# soundboard-qtpy-bff-v01.net
KiCad netlist of a schematic drawn in EAGLE
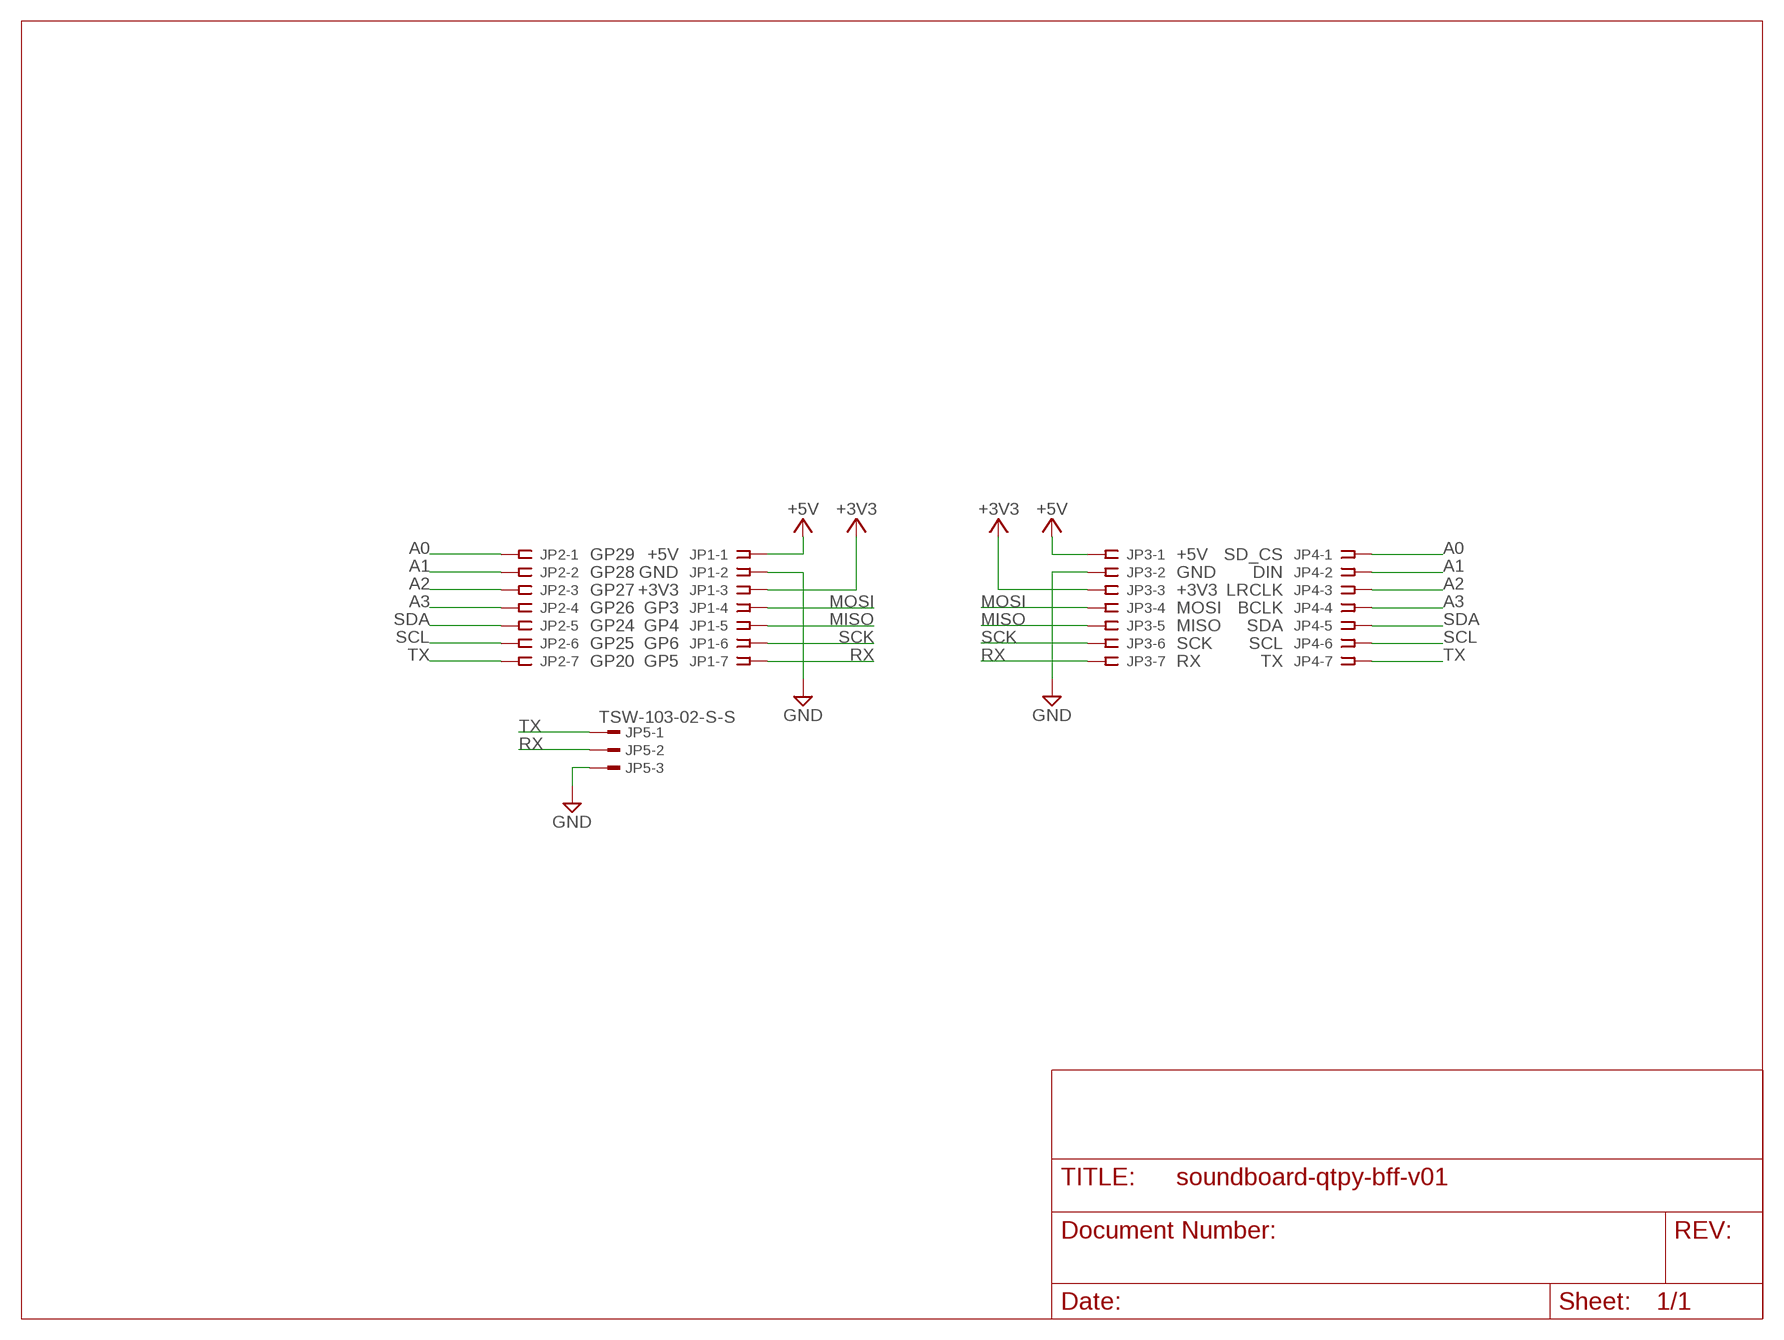
[diagram p0: schematic, sheet 1]

(export (version "E")
  (design (tool "Eeschema 10.0.6"))
  (components
    (comp (ref "JP1")
      (value "SSW-107-02-S-S")
      (footprint "eagle-import:SSW-107-02-S-S")
      (libsource (lib "eagle-import") (part "SSW-107-02-S-S"))
    )
    (comp (ref "JP2")
      (value "SSW-107-02-S-S")
      (footprint "eagle-import:SSW-107-02-S-S")
      (libsource (lib "eagle-import") (part "SSW-107-02-S-S"))
    )
    (comp (ref "JP3")
      (value "SSW-107-02-S-S")
      (footprint "eagle-import:SSW-107-02-S-S")
      (libsource (lib "eagle-import") (part "SSW-107-02-S-S"))
    )
    (comp (ref "JP4")
      (value "SSW-107-02-S-S")
      (footprint "eagle-import:SSW-107-02-S-S")
      (libsource (lib "eagle-import") (part "SSW-107-02-S-S"))
    )
    (comp (ref "JP5")
      (value "TSW-103-02-S-S")
      (footprint "eagle-import:TSW-103-02-S-S")
      (libsource (lib "eagle-import") (part "TSW-103-02-S-S"))
    )
  )
  (nets
    (net (code "1") (name "+3V3") (class "Default")
      (node (ref "JP1") (pin "3") (pinfunction "1_3") (pintype "passive"))
      (node (ref "JP3") (pin "3") (pinfunction "1_3") (pintype "passive"))
    )
    (net (code "2") (name "+5V") (class "Default")
      (node (ref "JP1") (pin "1") (pinfunction "1_1") (pintype "passive"))
      (node (ref "JP3") (pin "1") (pinfunction "1_1") (pintype "passive"))
    )
    (net (code "3") (name "/A0") (class "Default")
      (node (ref "JP2") (pin "1") (pinfunction "1_1") (pintype "passive"))
      (node (ref "JP4") (pin "1") (pinfunction "1_1") (pintype "passive"))
    )
    (net (code "4") (name "/A1") (class "Default")
      (node (ref "JP2") (pin "2") (pinfunction "1_2") (pintype "passive"))
      (node (ref "JP4") (pin "2") (pinfunction "1_2") (pintype "passive"))
    )
    (net (code "5") (name "/A2") (class "Default")
      (node (ref "JP2") (pin "3") (pinfunction "1_3") (pintype "passive"))
      (node (ref "JP4") (pin "3") (pinfunction "1_3") (pintype "passive"))
    )
    (net (code "6") (name "/A3") (class "Default")
      (node (ref "JP2") (pin "4") (pinfunction "1_4") (pintype "passive"))
      (node (ref "JP4") (pin "4") (pinfunction "1_4") (pintype "passive"))
    )
    (net (code "7") (name "/MISO") (class "Default")
      (node (ref "JP1") (pin "5") (pinfunction "1_5") (pintype "passive"))
      (node (ref "JP3") (pin "5") (pinfunction "1_5") (pintype "passive"))
    )
    (net (code "8") (name "/MOSI") (class "Default")
      (node (ref "JP1") (pin "4") (pinfunction "1_4") (pintype "passive"))
      (node (ref "JP3") (pin "4") (pinfunction "1_4") (pintype "passive"))
    )
    (net (code "9") (name "/RX") (class "Default")
      (node (ref "JP1") (pin "7") (pinfunction "1_7") (pintype "passive"))
      (node (ref "JP3") (pin "7") (pinfunction "1_7") (pintype "passive"))
      (node (ref "JP5") (pin "2") (pinfunction "1_2") (pintype "passive"))
    )
    (net (code "10") (name "/SCK") (class "Default")
      (node (ref "JP1") (pin "6") (pinfunction "1_6") (pintype "passive"))
      (node (ref "JP3") (pin "6") (pinfunction "1_6") (pintype "passive"))
    )
    (net (code "11") (name "/SCL") (class "Default")
      (node (ref "JP2") (pin "6") (pinfunction "1_6") (pintype "passive"))
      (node (ref "JP4") (pin "6") (pinfunction "1_6") (pintype "passive"))
    )
    (net (code "12") (name "/SDA") (class "Default")
      (node (ref "JP2") (pin "5") (pinfunction "1_5") (pintype "passive"))
      (node (ref "JP4") (pin "5") (pinfunction "1_5") (pintype "passive"))
    )
    (net (code "13") (name "/TX") (class "Default")
      (node (ref "JP2") (pin "7") (pinfunction "1_7") (pintype "passive"))
      (node (ref "JP4") (pin "7") (pinfunction "1_7") (pintype "passive"))
      (node (ref "JP5") (pin "1") (pinfunction "1_1") (pintype "passive"))
    )
    (net (code "14") (name "GND") (class "Default")
      (node (ref "JP1") (pin "2") (pinfunction "1_2") (pintype "passive"))
      (node (ref "JP3") (pin "2") (pinfunction "1_2") (pintype "passive"))
      (node (ref "JP5") (pin "3") (pinfunction "1_3") (pintype "passive"))
    )
  )
)
